# LB_BIT_o1_LED-v02_rev1.net
KiCad netlist of a schematic drawn in EAGLE
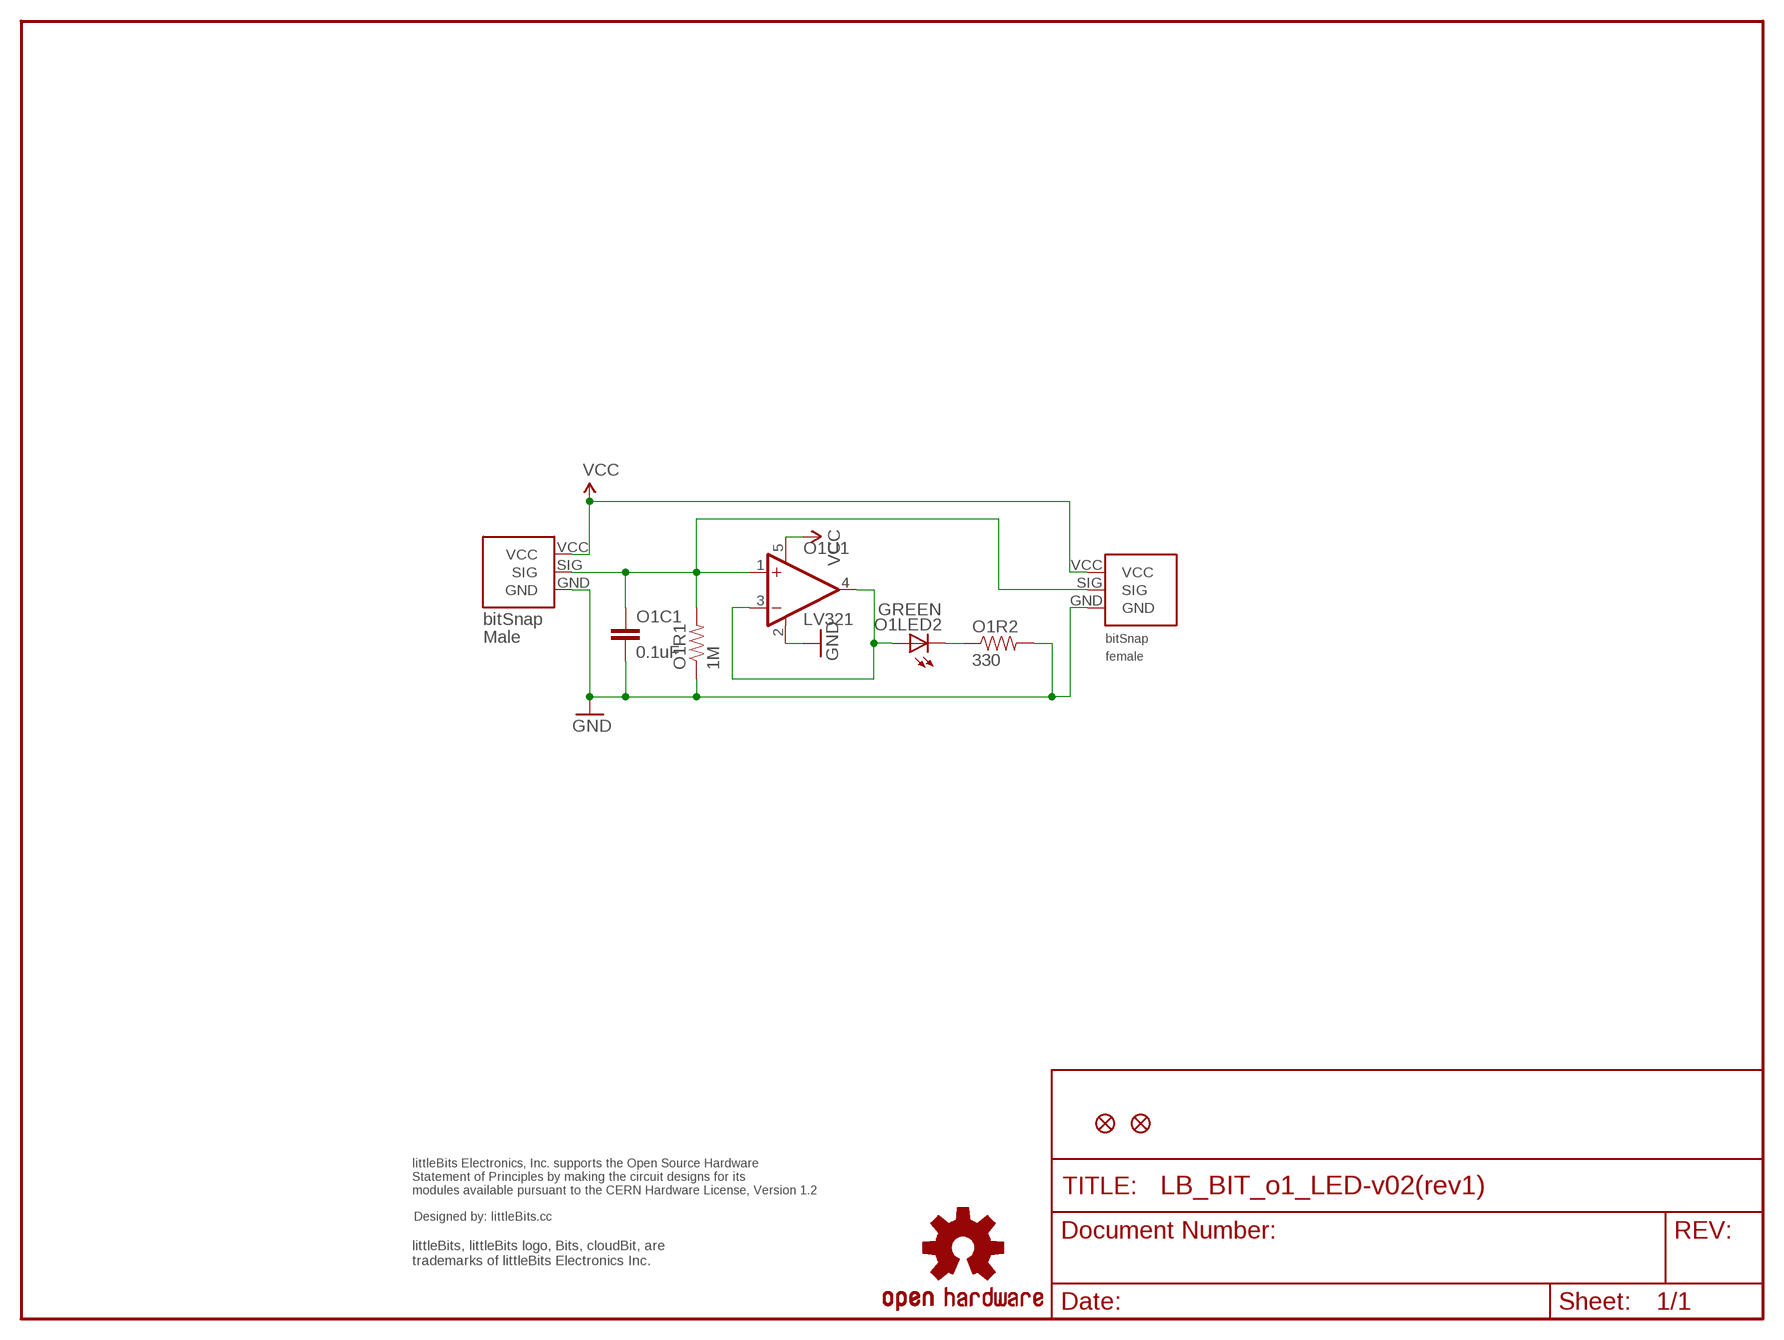
[diagram p0: schematic, sheet 1]

(export (version "E")
  (design (tool "Eeschema 10.0.6"))
  (components
    (comp (ref "JP1")
      (value "FIDUCIAL1X2.5")
      (footprint "eagle-import:FIDUCIAL-1X2.5")
      (libsource (lib "eagle-import") (part "FIDUCIAL1X2.5"))
    )
    (comp (ref "JP2")
      (value "FIDUCIAL1X2.5")
      (footprint "eagle-import:FIDUCIAL-1X2.5")
      (libsource (lib "eagle-import") (part "FIDUCIAL1X2.5"))
    )
    (comp (ref "O1BSF")
      (value "BITSNAP_FEMALE")
      (footprint "eagle-import:BITSNAP_FEMALE")
      (libsource (lib "eagle-import") (part "BITSNAP_FEMALE"))
    )
    (comp (ref "O1BSM")
      (value "BITSNAP_MALE")
      (footprint "eagle-import:BITSNAP_MALE")
      (libsource (lib "eagle-import") (part "BITSNAP_MALE"))
    )
    (comp (ref "O1C1")
      (value "0.1uF")
      (footprint "eagle-import:0603-CAP")
      (libsource (lib "eagle-import") (part "CAP0603-CAP"))
    )
    (comp (ref "O1LED2")
      (value "GREEN")
      (footprint "eagle-import:LED-1206")
      (libsource (lib "eagle-import") (part "LED1206"))
    )
    (comp (ref "O1R1")
      (value "1M")
      (footprint "eagle-import:0603-RES")
      (libsource (lib "eagle-import") (part "RESISTOR0603-RES"))
    )
    (comp (ref "O1R2")
      (value "330")
      (footprint "eagle-import:0603-RES")
      (libsource (lib "eagle-import") (part "RESISTOR0603-RES"))
    )
    (comp (ref "O1U1")
      (value "LV321")
      (footprint "eagle-import:SC70-5")
      (libsource (lib "eagle-import") (part "LV321"))
    )
    (comp (ref "U$1")
      (value "OSHWCREDIT")
      (footprint "eagle-import:OSHWCREDIT")
      (libsource (lib "eagle-import") (part "OSHWCREDIT"))
    )
    (comp (ref "U$3")
      (value "OSHW-LOGOL")
      (footprint "eagle-import:OSHW-LOGO-L")
      (libsource (lib "eagle-import") (part "OSHW-LOGOL"))
    )
  )
  (nets
    (net (code "1") (name "GND") (class "Default")
      (node (ref "O1BSF") (pin "GND") (pinfunction "GND_GND") (pintype "bidirectional"))
      (node (ref "O1BSM") (pin "GND") (pinfunction "GND_GND") (pintype "bidirectional"))
      (node (ref "O1C1") (pin "2") (pinfunction "2_2") (pintype "passive"))
      (node (ref "O1R1") (pin "1") (pinfunction "1_1") (pintype "passive"))
      (node (ref "O1R2") (pin "2") (pinfunction "2_2") (pintype "passive"))
      (node (ref "O1U1") (pin "2") (pinfunction "V-_2") (pintype "power_in"))
    )
    (net (code "2") (name "Net-(O1LED2-PadC)") (class "Default")
      (node (ref "O1LED2") (pin "C") (pinfunction "C_C") (pintype "passive"))
      (node (ref "O1R2") (pin "1") (pinfunction "1_1") (pintype "passive"))
    )
    (net (code "3") (name "Net-(O1U1-+IN)") (class "Default")
      (node (ref "O1BSF") (pin "SIG") (pinfunction "SIG_SIG") (pintype "bidirectional"))
      (node (ref "O1BSM") (pin "SIG") (pinfunction "SIG_SIG") (pintype "bidirectional"))
      (node (ref "O1C1") (pin "1") (pinfunction "1_1") (pintype "passive"))
      (node (ref "O1R1") (pin "2") (pinfunction "2_2") (pintype "passive"))
      (node (ref "O1U1") (pin "1") (pinfunction "+IN_1") (pintype "input"))
    )
    (net (code "4") (name "Net-(O1U1--IN)") (class "Default")
      (node (ref "O1LED2") (pin "A") (pinfunction "A_A") (pintype "passive"))
      (node (ref "O1U1") (pin "3") (pinfunction "-IN_3") (pintype "input"))
      (node (ref "O1U1") (pin "4") (pinfunction "OUT_4") (pintype "output"))
    )
    (net (code "5") (name "VCC") (class "Default")
      (node (ref "O1BSF") (pin "VCC") (pinfunction "VCC_VCC") (pintype "bidirectional"))
      (node (ref "O1BSM") (pin "VCC") (pinfunction "VCC_VCC") (pintype "bidirectional"))
      (node (ref "O1U1") (pin "5") (pinfunction "V+_5") (pintype "power_in"))
    )
  )
)
